# SNES-ModChip-v1.net
KiCad netlist of a schematic drawn in EAGLE
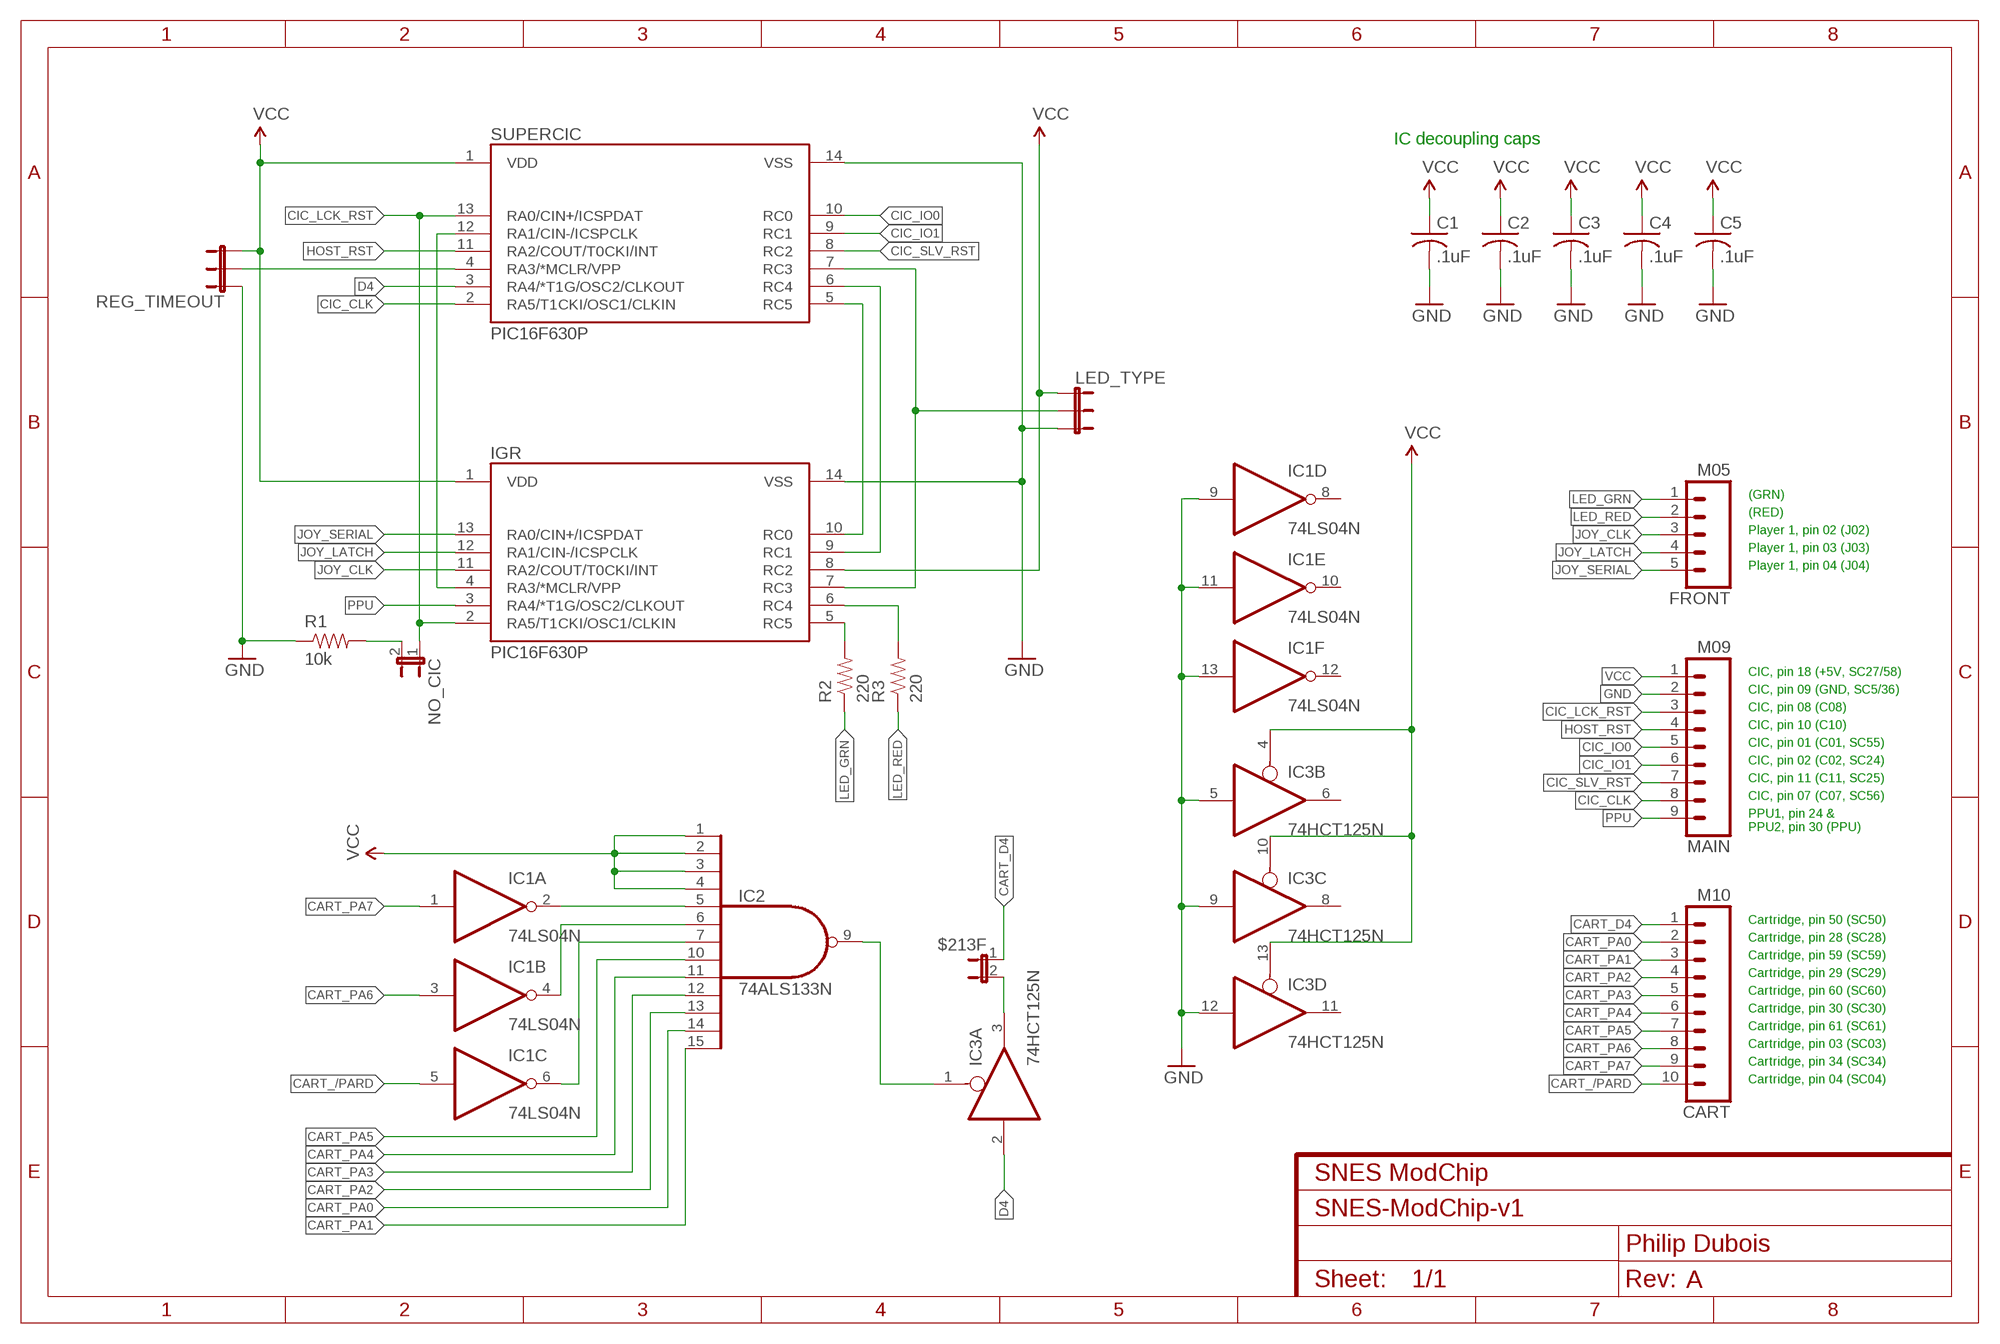
[diagram p0: schematic, sheet 1]

(export (version "E")
  (design (tool "Eeschema 10.0.6"))
  (components
    (comp (ref "$213F")
      (value "JUMPER-2PTH")
      (footprint "eagle-import:1X02")
      (libsource (lib "eagle-import") (part "JUMPER-2PTH"))
    )
    (comp (ref "C1")
      (value ".1uF")
      (footprint "eagle-import:C050-025X075")
      (libsource (lib "eagle-import") (part "C-US050-025X075"))
    )
    (comp (ref "C2")
      (value ".1uF")
      (footprint "eagle-import:C050-025X075")
      (libsource (lib "eagle-import") (part "C-US050-025X075"))
    )
    (comp (ref "C3")
      (value ".1uF")
      (footprint "eagle-import:C050-025X075")
      (libsource (lib "eagle-import") (part "C-US050-025X075"))
    )
    (comp (ref "C4")
      (value ".1uF")
      (footprint "eagle-import:C050-025X075")
      (libsource (lib "eagle-import") (part "C-US050-025X075"))
    )
    (comp (ref "C5")
      (value ".1uF")
      (footprint "eagle-import:C050-025X075")
      (libsource (lib "eagle-import") (part "C-US050-025X075"))
    )
    (comp (ref "CART")
      (value "M10")
      (footprint "eagle-import:1X10")
      (libsource (lib "eagle-import") (part "M10"))
    )
    (comp (ref "FRONT")
      (value "M05")
      (footprint "eagle-import:1X05")
      (libsource (lib "eagle-import") (part "M05"))
    )
    (comp (ref "IC1")
      (value "74LS04N")
      (footprint "eagle-import:DIL14")
      (libsource (lib "eagle-import") (part "7404NLS"))
    )
    (comp (ref "IC2")
      (value "74ALS133N")
      (footprint "eagle-import:DIL16")
      (libsource (lib "eagle-import") (part "74133NALS"))
    )
    (comp (ref "IC3")
      (value "74HCT125N")
      (footprint "eagle-import:DIL14")
      (libsource (lib "eagle-import") (part "74125NHCT"))
    )
    (comp (ref "IGR")
      (value "PIC16F630P")
      (footprint "eagle-import:DIL14")
      (libsource (lib "eagle-import") (part "PIC16F630P"))
    )
    (comp (ref "LED_TYPE")
      (value "JUMPER-3PTH")
      (footprint "eagle-import:1X03")
      (libsource (lib "eagle-import") (part "JUMPER-3PTH"))
    )
    (comp (ref "MAIN")
      (value "M09")
      (footprint "eagle-import:1X09")
      (libsource (lib "eagle-import") (part "M09"))
    )
    (comp (ref "NO_CIC")
      (value "JUMPER-2PTH")
      (footprint "eagle-import:1X02")
      (libsource (lib "eagle-import") (part "JUMPER-2PTH"))
    )
    (comp (ref "R1")
      (value "10k")
      (footprint "eagle-import:AXIAL-0.3")
      (libsource (lib "eagle-import") (part "RESISTORPTH"))
    )
    (comp (ref "R2")
      (value "220")
      (footprint "eagle-import:AXIAL-0.3")
      (libsource (lib "eagle-import") (part "RESISTORPTH"))
    )
    (comp (ref "R3")
      (value "220")
      (footprint "eagle-import:AXIAL-0.3")
      (libsource (lib "eagle-import") (part "RESISTORPTH"))
    )
    (comp (ref "REG_TIMEOUT")
      (value "JUMPER-3PTH")
      (footprint "eagle-import:1X03")
      (libsource (lib "eagle-import") (part "JUMPER-3PTH"))
    )
    (comp (ref "SUPERCIC")
      (value "PIC16F630P")
      (footprint "eagle-import:DIL14")
      (libsource (lib "eagle-import") (part "PIC16F630P"))
    )
  )
  (nets
    (net (code "1") (name "CART_D4") (class "Default")
      (node (ref "$213F") (pin "1") (pinfunction "1_1") (pintype "passive"))
      (node (ref "CART") (pin "1") (pinfunction "1_1") (pintype "passive"))
    )
    (net (code "2") (name "CART_PA0") (class "Default")
      (node (ref "CART") (pin "2") (pinfunction "2_2") (pintype "passive"))
      (node (ref "IC2") (pin "14") (pinfunction "I11_14") (pintype "input"))
    )
    (net (code "3") (name "CART_PA1") (class "Default")
      (node (ref "CART") (pin "3") (pinfunction "3_3") (pintype "passive"))
      (node (ref "IC2") (pin "15") (pinfunction "I12_15") (pintype "input"))
    )
    (net (code "4") (name "CART_PA2") (class "Default")
      (node (ref "CART") (pin "4") (pinfunction "4_4") (pintype "passive"))
      (node (ref "IC2") (pin "13") (pinfunction "I10_13") (pintype "input"))
    )
    (net (code "5") (name "CART_PA3") (class "Default")
      (node (ref "CART") (pin "5") (pinfunction "5_5") (pintype "passive"))
      (node (ref "IC2") (pin "12") (pinfunction "I9_12") (pintype "input"))
    )
    (net (code "6") (name "CART_PA4") (class "Default")
      (node (ref "CART") (pin "6") (pinfunction "6_6") (pintype "passive"))
      (node (ref "IC2") (pin "11") (pinfunction "I8_11") (pintype "input"))
    )
    (net (code "7") (name "CART_PA5") (class "Default")
      (node (ref "CART") (pin "7") (pinfunction "7_7") (pintype "passive"))
      (node (ref "IC2") (pin "10") (pinfunction "I7_10") (pintype "input"))
    )
    (net (code "8") (name "CART_PA6") (class "Default")
      (node (ref "CART") (pin "8") (pinfunction "8_8") (pintype "passive"))
      (node (ref "IC1") (pin "3") (pinfunction "I_3") (pintype "input"))
    )
    (net (code "9") (name "CART_PA7") (class "Default")
      (node (ref "CART") (pin "9") (pinfunction "9_9") (pintype "passive"))
      (node (ref "IC1") (pin "1") (pinfunction "I_1") (pintype "input"))
    )
    (net (code "10") (name "CART_{slash}PARD") (class "Default")
      (node (ref "CART") (pin "10") (pinfunction "10_10") (pintype "passive"))
      (node (ref "IC1") (pin "5") (pinfunction "I_5") (pintype "input"))
    )
    (net (code "11") (name "CIC_CLK") (class "Default")
      (node (ref "MAIN") (pin "8") (pinfunction "8_8") (pintype "passive"))
      (node (ref "SUPERCIC") (pin "2") (pinfunction "RA5/T1CKI/OSC1/CLKIN_2") (pintype "bidirectional"))
    )
    (net (code "12") (name "CIC_IO0") (class "Default")
      (node (ref "MAIN") (pin "5") (pinfunction "5_5") (pintype "passive"))
      (node (ref "SUPERCIC") (pin "10") (pinfunction "RC0_10") (pintype "bidirectional"))
    )
    (net (code "13") (name "CIC_IO1") (class "Default")
      (node (ref "MAIN") (pin "6") (pinfunction "6_6") (pintype "passive"))
      (node (ref "SUPERCIC") (pin "9") (pinfunction "RC1_9") (pintype "bidirectional"))
    )
    (net (code "14") (name "CIC_LCK_RST") (class "Default")
      (node (ref "IGR") (pin "2") (pinfunction "RA5/T1CKI/OSC1/CLKIN_2") (pintype "bidirectional"))
      (node (ref "MAIN") (pin "3") (pinfunction "3_3") (pintype "passive"))
      (node (ref "NO_CIC") (pin "1") (pinfunction "1_1") (pintype "passive"))
      (node (ref "SUPERCIC") (pin "13") (pinfunction "RA0/CIN+/ICSPDAT_13") (pintype "bidirectional"))
    )
    (net (code "15") (name "CIC_SLV_RST") (class "Default")
      (node (ref "MAIN") (pin "7") (pinfunction "7_7") (pintype "passive"))
      (node (ref "SUPERCIC") (pin "8") (pinfunction "RC2_8") (pintype "bidirectional"))
    )
    (net (code "16") (name "D4") (class "Default")
      (node (ref "IC3") (pin "2") (pinfunction "I_2") (pintype "input"))
      (node (ref "SUPERCIC") (pin "3") (pinfunction "RA4/*T1G/OSC2/CLKOUT_3") (pintype "bidirectional"))
    )
    (net (code "17") (name "GND") (class "Default")
      (node (ref "C1") (pin "2") (pinfunction "2_2") (pintype "passive"))
      (node (ref "C2") (pin "2") (pinfunction "2_2") (pintype "passive"))
      (node (ref "C3") (pin "2") (pinfunction "2_2") (pintype "passive"))
      (node (ref "C4") (pin "2") (pinfunction "2_2") (pintype "passive"))
      (node (ref "C5") (pin "2") (pinfunction "2_2") (pintype "passive"))
      (node (ref "IC1") (pin "11") (pinfunction "I_11") (pintype "input"))
      (node (ref "IC1") (pin "13") (pinfunction "I_13") (pintype "input"))
      (node (ref "IC1") (pin "9") (pinfunction "I_9") (pintype "input"))
      (node (ref "IC3") (pin "12") (pinfunction "I_12") (pintype "input"))
      (node (ref "IC3") (pin "5") (pinfunction "I_5") (pintype "input"))
      (node (ref "IC3") (pin "9") (pinfunction "I_9") (pintype "input"))
      (node (ref "IGR") (pin "14") (pinfunction "VSS_14") (pintype "power_in"))
      (node (ref "LED_TYPE") (pin "3") (pinfunction "3_3") (pintype "passive"))
      (node (ref "MAIN") (pin "2") (pinfunction "2_2") (pintype "passive"))
      (node (ref "R1") (pin "P$1") (pinfunction "1_P$1") (pintype "passive"))
      (node (ref "REG_TIMEOUT") (pin "1") (pinfunction "1_1") (pintype "passive"))
      (node (ref "SUPERCIC") (pin "14") (pinfunction "VSS_14") (pintype "power_in"))
    )
    (net (code "18") (name "HOST_RST") (class "Default")
      (node (ref "MAIN") (pin "4") (pinfunction "4_4") (pintype "passive"))
      (node (ref "SUPERCIC") (pin "11") (pinfunction "RA2/COUT/T0CKI/INT_11") (pintype "bidirectional"))
    )
    (net (code "19") (name "JOY_CLK") (class "Default")
      (node (ref "FRONT") (pin "3") (pinfunction "3_3") (pintype "passive"))
      (node (ref "IGR") (pin "11") (pinfunction "RA2/COUT/T0CKI/INT_11") (pintype "bidirectional"))
    )
    (net (code "20") (name "JOY_LATCH") (class "Default")
      (node (ref "FRONT") (pin "4") (pinfunction "4_4") (pintype "passive"))
      (node (ref "IGR") (pin "12") (pinfunction "RA1/CIN-/ICSPCLK_12") (pintype "bidirectional"))
    )
    (net (code "21") (name "JOY_SERIAL") (class "Default")
      (node (ref "FRONT") (pin "5") (pinfunction "5_5") (pintype "passive"))
      (node (ref "IGR") (pin "13") (pinfunction "RA0/CIN+/ICSPDAT_13") (pintype "bidirectional"))
    )
    (net (code "22") (name "LED_GRN") (class "Default")
      (node (ref "FRONT") (pin "1") (pinfunction "1_1") (pintype "passive"))
      (node (ref "R2") (pin "P$1") (pinfunction "1_P$1") (pintype "passive"))
    )
    (net (code "23") (name "LED_RED") (class "Default")
      (node (ref "FRONT") (pin "2") (pinfunction "2_2") (pintype "passive"))
      (node (ref "R3") (pin "P$1") (pinfunction "1_P$1") (pintype "passive"))
    )
    (net (code "24") (name "Net-(IC1A-O)") (class "Default")
      (node (ref "IC1") (pin "2") (pinfunction "O_2") (pintype "output"))
      (node (ref "IC2") (pin "5") (pinfunction "I4_5") (pintype "input"))
    )
    (net (code "25") (name "Net-(IC1B-O)") (class "Default")
      (node (ref "IC1") (pin "4") (pinfunction "O_4") (pintype "output"))
      (node (ref "IC2") (pin "6") (pinfunction "I5_6") (pintype "input"))
    )
    (net (code "26") (name "Net-(IC1C-O)") (class "Default")
      (node (ref "IC1") (pin "6") (pinfunction "O_6") (pintype "output"))
      (node (ref "IC2") (pin "7") (pinfunction "I6_7") (pintype "input"))
    )
    (net (code "27") (name "Net-(IC2A-O)") (class "Default")
      (node (ref "IC2") (pin "9") (pinfunction "O_9") (pintype "output"))
      (node (ref "IC3") (pin "1") (pinfunction "OE_1") (pintype "input"))
    )
    (net (code "28") (name "Net-(IC3A-O)") (class "Default")
      (node (ref "$213F") (pin "2") (pinfunction "2_2") (pintype "passive"))
      (node (ref "IC3") (pin "3") (pinfunction "O_3") (pintype "tri_state"))
    )
    (net (code "29") (name "Net-(IGR-RA3{slash}*MCLR{slash}VPP)") (class "Default")
      (node (ref "IGR") (pin "4") (pinfunction "RA3/*MCLR/VPP_4") (pintype "bidirectional"))
      (node (ref "SUPERCIC") (pin "12") (pinfunction "RA1/CIN-/ICSPCLK_12") (pintype "bidirectional"))
    )
    (net (code "30") (name "Net-(IGR-RC0)") (class "Default")
      (node (ref "IGR") (pin "10") (pinfunction "RC0_10") (pintype "bidirectional"))
      (node (ref "SUPERCIC") (pin "5") (pinfunction "RC5_5") (pintype "bidirectional"))
    )
    (net (code "31") (name "Net-(IGR-RC1)") (class "Default")
      (node (ref "IGR") (pin "9") (pinfunction "RC1_9") (pintype "bidirectional"))
      (node (ref "SUPERCIC") (pin "6") (pinfunction "RC4_6") (pintype "bidirectional"))
    )
    (net (code "32") (name "Net-(IGR-RC3)") (class "Default")
      (node (ref "IGR") (pin "7") (pinfunction "RC3_7") (pintype "bidirectional"))
      (node (ref "LED_TYPE") (pin "2") (pinfunction "2_2") (pintype "passive"))
      (node (ref "SUPERCIC") (pin "7") (pinfunction "RC3_7") (pintype "bidirectional"))
    )
    (net (code "33") (name "Net-(IGR-RC4)") (class "Default")
      (node (ref "IGR") (pin "6") (pinfunction "RC4_6") (pintype "bidirectional"))
      (node (ref "R3") (pin "P$2") (pinfunction "2_P$2") (pintype "passive"))
    )
    (net (code "34") (name "Net-(IGR-RC5)") (class "Default")
      (node (ref "IGR") (pin "5") (pinfunction "RC5_5") (pintype "bidirectional"))
      (node (ref "R2") (pin "P$2") (pinfunction "2_P$2") (pintype "passive"))
    )
    (net (code "35") (name "Net-(R1-2)") (class "Default")
      (node (ref "NO_CIC") (pin "2") (pinfunction "2_2") (pintype "passive"))
      (node (ref "R1") (pin "P$2") (pinfunction "2_P$2") (pintype "passive"))
    )
    (net (code "36") (name "Net-(SUPERCIC-RA3{slash}*MCLR{slash}VPP)") (class "Default")
      (node (ref "REG_TIMEOUT") (pin "2") (pinfunction "2_2") (pintype "passive"))
      (node (ref "SUPERCIC") (pin "4") (pinfunction "RA3/*MCLR/VPP_4") (pintype "bidirectional"))
    )
    (net (code "37") (name "PPU") (class "Default")
      (node (ref "IGR") (pin "3") (pinfunction "RA4/*T1G/OSC2/CLKOUT_3") (pintype "bidirectional"))
      (node (ref "MAIN") (pin "9") (pinfunction "9_9") (pintype "passive"))
    )
    (net (code "38") (name "VCC") (class "Default")
      (node (ref "C1") (pin "1") (pinfunction "1_1") (pintype "passive"))
      (node (ref "C2") (pin "1") (pinfunction "1_1") (pintype "passive"))
      (node (ref "C3") (pin "1") (pinfunction "1_1") (pintype "passive"))
      (node (ref "C4") (pin "1") (pinfunction "1_1") (pintype "passive"))
      (node (ref "C5") (pin "1") (pinfunction "1_1") (pintype "passive"))
      (node (ref "IC2") (pin "1") (pinfunction "I0_1") (pintype "input"))
      (node (ref "IC2") (pin "2") (pinfunction "I1_2") (pintype "input"))
      (node (ref "IC2") (pin "3") (pinfunction "I2_3") (pintype "input"))
      (node (ref "IC2") (pin "4") (pinfunction "I3_4") (pintype "input"))
      (node (ref "IC3") (pin "10") (pinfunction "OE_10") (pintype "input"))
      (node (ref "IC3") (pin "13") (pinfunction "OE_13") (pintype "input"))
      (node (ref "IC3") (pin "4") (pinfunction "OE_4") (pintype "input"))
      (node (ref "IGR") (pin "1") (pinfunction "VDD_1") (pintype "power_in"))
      (node (ref "IGR") (pin "8") (pinfunction "RC2_8") (pintype "bidirectional"))
      (node (ref "LED_TYPE") (pin "1") (pinfunction "1_1") (pintype "passive"))
      (node (ref "MAIN") (pin "1") (pinfunction "1_1") (pintype "passive"))
      (node (ref "REG_TIMEOUT") (pin "3") (pinfunction "3_3") (pintype "passive"))
      (node (ref "SUPERCIC") (pin "1") (pinfunction "VDD_1") (pintype "power_in"))
    )
    (net (code "39") (name "unconnected-(IC1D-O-Pad8)") (class "Default")
      (node (ref "IC1") (pin "8") (pinfunction "O_8") (pintype "output"))
    )
    (net (code "40") (name "unconnected-(IC1E-O-Pad10)") (class "Default")
      (node (ref "IC1") (pin "10") (pinfunction "O_10") (pintype "output"))
    )
    (net (code "41") (name "unconnected-(IC1F-O-Pad12)") (class "Default")
      (node (ref "IC1") (pin "12") (pinfunction "O_12") (pintype "output"))
    )
    (net (code "42") (name "unconnected-(IC3B-O-Pad6)") (class "Default")
      (node (ref "IC3") (pin "6") (pinfunction "O_6") (pintype "tri_state"))
    )
    (net (code "43") (name "unconnected-(IC3C-O-Pad8)") (class "Default")
      (node (ref "IC3") (pin "8") (pinfunction "O_8") (pintype "tri_state"))
    )
    (net (code "44") (name "unconnected-(IC3D-O-Pad11)") (class "Default")
      (node (ref "IC3") (pin "11") (pinfunction "O_11") (pintype "tri_state"))
    )
  )
)
